# FEU3.net
KiCad netlist of a schematic drawn in EAGLE
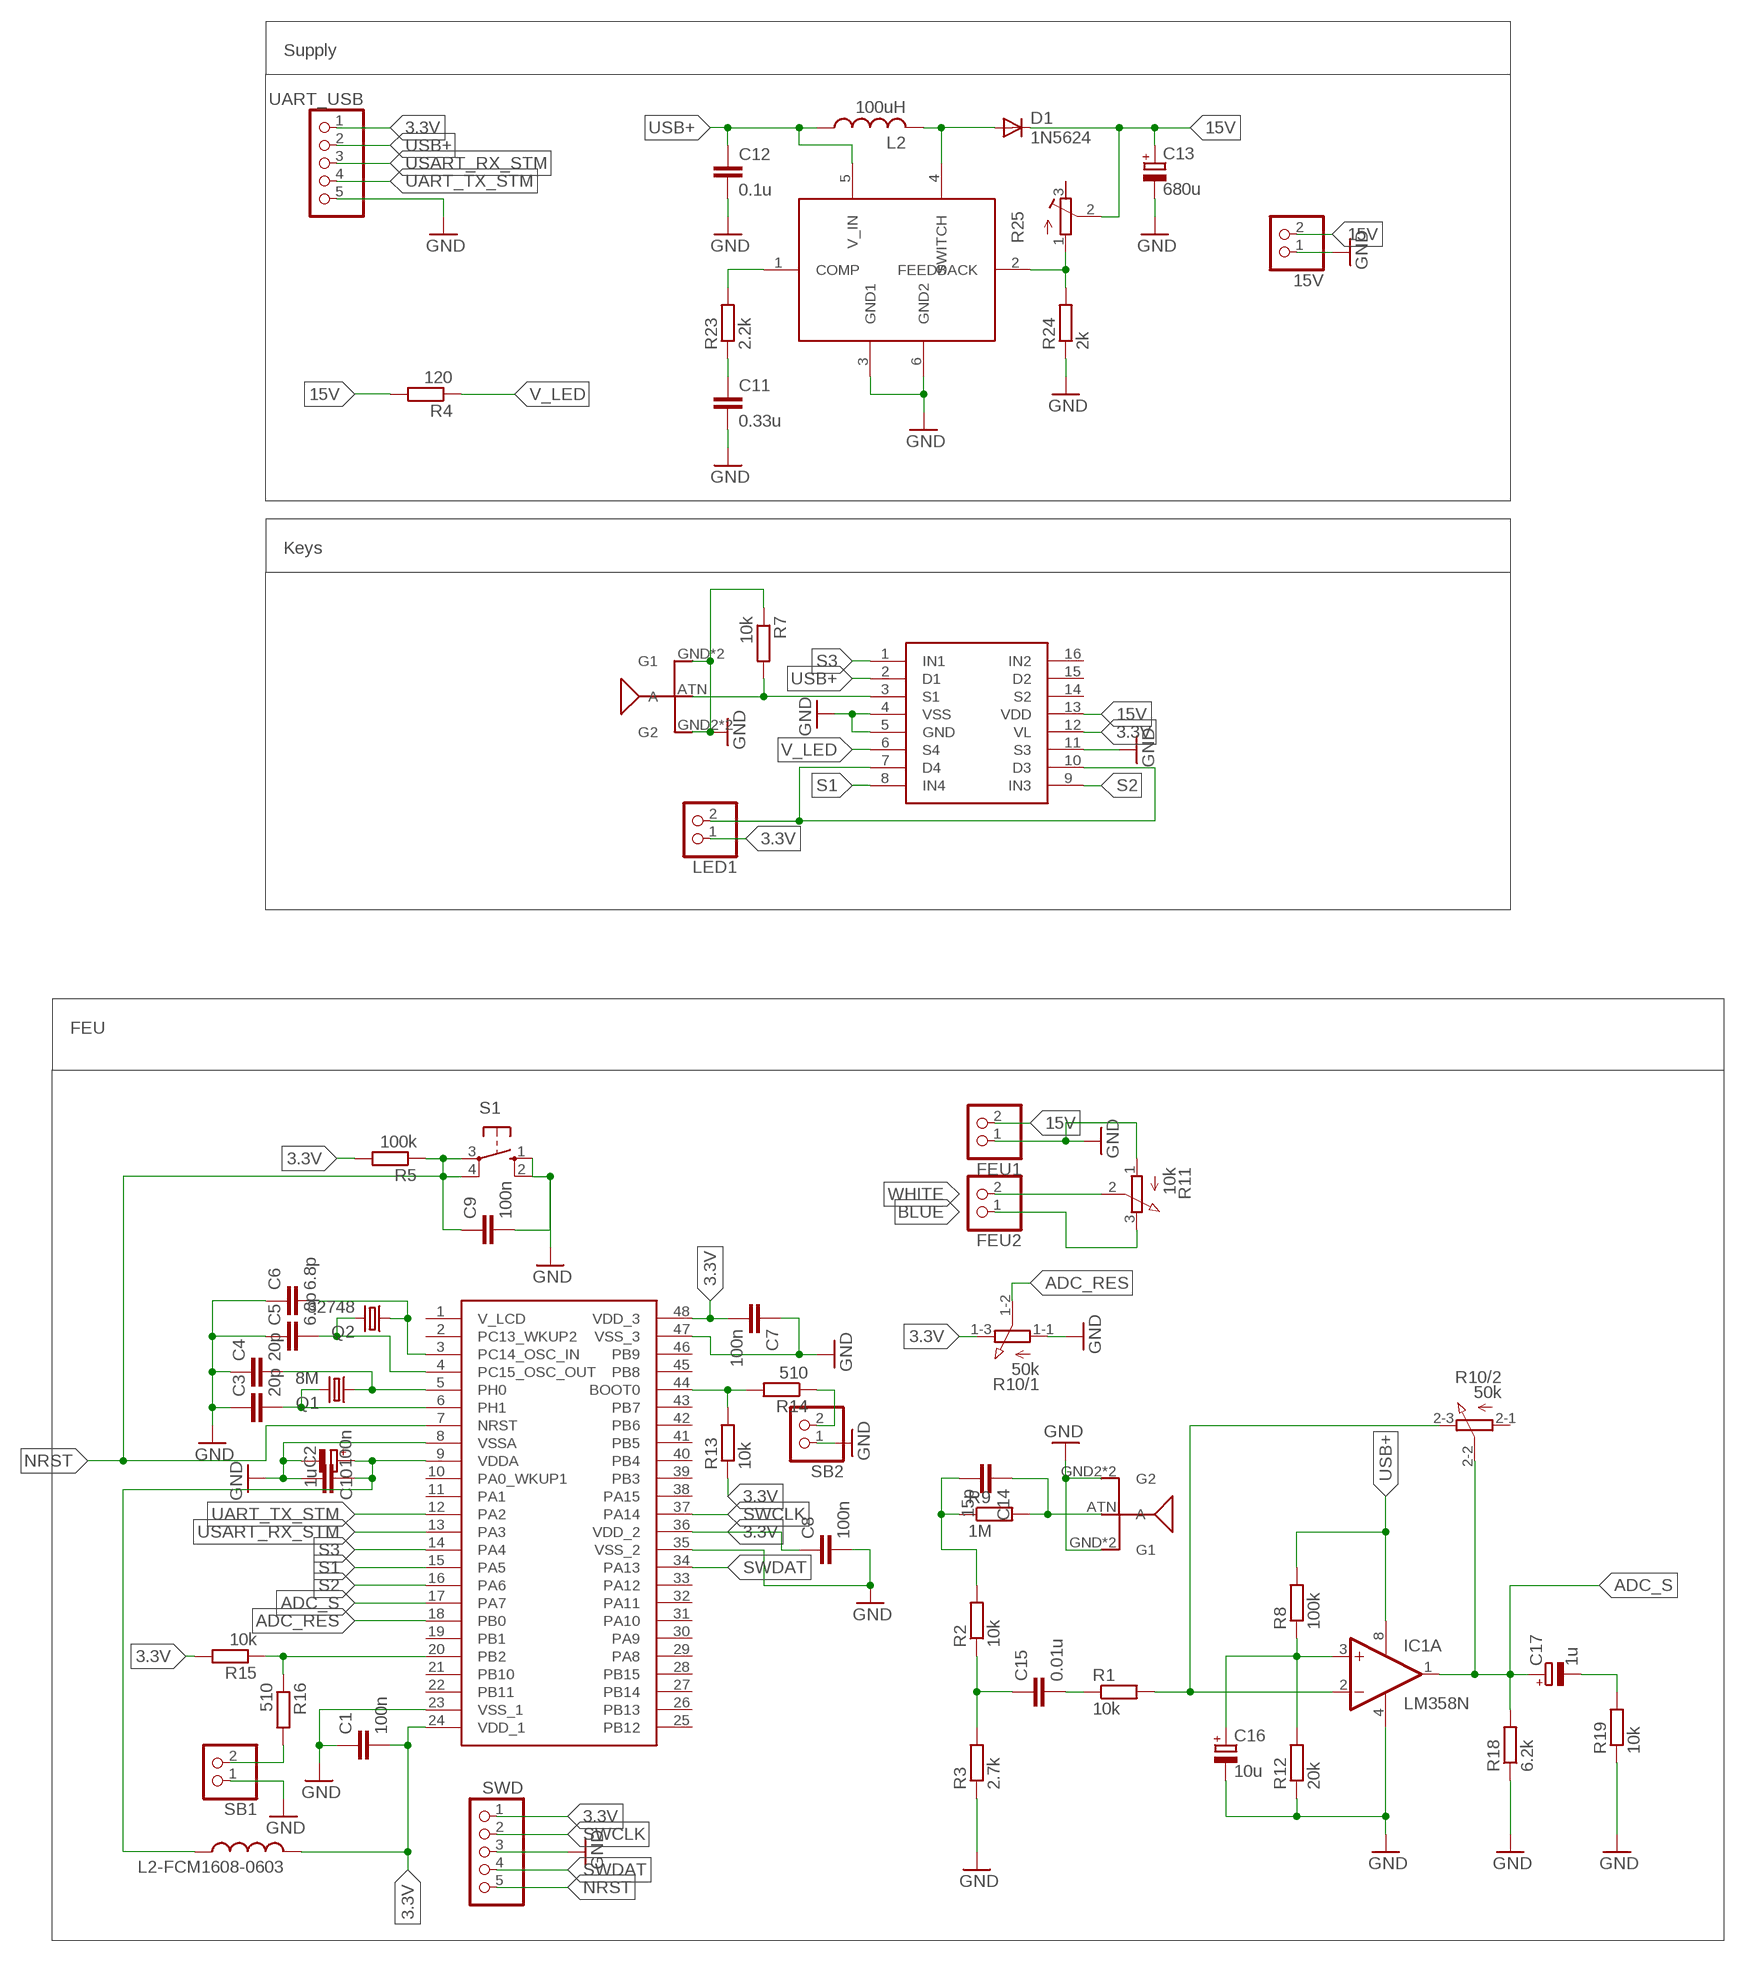
[diagram p0: schematic, sheet 1]

(export (version "E")
  (design (tool "Eeschema 10.0.6"))
  (components
    (comp (ref "15V")
      (value "PINHD-1X2")
      (footprint "eagle-import:1X02")
      (libsource (lib "eagle-import") (part "PINHD-1X2"))
    )
    (comp (ref "C1")
      (value "100n")
      (footprint "eagle-import:C0805")
      (libsource (lib "eagle-import") (part "C-EUC0805"))
    )
    (comp (ref "C2")
      (value "100n")
      (footprint "eagle-import:C0805")
      (libsource (lib "eagle-import") (part "C-EUC0805"))
    )
    (comp (ref "C3")
      (value "20p")
      (footprint "eagle-import:C0805")
      (libsource (lib "eagle-import") (part "C-EUC0805"))
    )
    (comp (ref "C4")
      (value "20p")
      (footprint "eagle-import:C0805")
      (libsource (lib "eagle-import") (part "C-EUC0805"))
    )
    (comp (ref "C5")
      (value "6.8p")
      (footprint "eagle-import:C0805")
      (libsource (lib "eagle-import") (part "C-EUC0805"))
    )
    (comp (ref "C6")
      (value "6.8p")
      (footprint "eagle-import:C0805")
      (libsource (lib "eagle-import") (part "C-EUC0805"))
    )
    (comp (ref "C7")
      (value "100n")
      (footprint "eagle-import:C0805")
      (libsource (lib "eagle-import") (part "C-EUC0805"))
    )
    (comp (ref "C8")
      (value "100n")
      (footprint "eagle-import:C0805")
      (libsource (lib "eagle-import") (part "C-EUC0805"))
    )
    (comp (ref "C9")
      (value "100n")
      (footprint "eagle-import:C0805")
      (libsource (lib "eagle-import") (part "C-EUC0805"))
    )
    (comp (ref "C10")
      (value "1u")
      (footprint "eagle-import:A_3216-18W")
      (libsource (lib "eagle-import") (part "CPOL-EUA/3216-18W"))
    )
    (comp (ref "C11")
      (value "0.33u")
      (footprint "eagle-import:C0805")
      (libsource (lib "eagle-import") (part "C-EUC0805"))
    )
    (comp (ref "C12")
      (value "0.1u")
      (footprint "eagle-import:C0805")
      (libsource (lib "eagle-import") (part "C-EUC0805"))
    )
    (comp (ref "C13")
      (value "680u")
      (footprint "eagle-import:E5-5")
      (libsource (lib "eagle-import") (part "CPOL-EUE5-5"))
    )
    (comp (ref "C14")
      (value "15p")
      (footprint "eagle-import:C0805")
      (libsource (lib "eagle-import") (part "C-EUC0805"))
    )
    (comp (ref "C15")
      (value "0.01u")
      (footprint "eagle-import:C0805")
      (libsource (lib "eagle-import") (part "C-EUC0805"))
    )
    (comp (ref "C16")
      (value "10u")
      (footprint "eagle-import:E3,5-8")
      (libsource (lib "eagle-import") (part "CPOL-EUE3.5-8"))
    )
    (comp (ref "C17")
      (value "1u")
      (footprint "eagle-import:E3,5-8")
      (libsource (lib "eagle-import") (part "CPOL-EUE3.5-8"))
    )
    (comp (ref "D1")
      (value "1N5624")
      (footprint "eagle-import:DO201-15")
      (libsource (lib "eagle-import") (part "1N5624"))
    )
    (comp (ref "FEU1")
      (value "PINHD-1X2")
      (footprint "eagle-import:1X02")
      (libsource (lib "eagle-import") (part "PINHD-1X2"))
    )
    (comp (ref "FEU2")
      (value "PINHD-1X2")
      (footprint "eagle-import:1X02")
      (libsource (lib "eagle-import") (part "PINHD-1X2"))
    )
    (comp (ref "IC1")
      (value "LM358N")
      (footprint "eagle-import:DIL08")
      (libsource (lib "eagle-import") (part "LM358N"))
    )
    (comp (ref "L2")
      (value "100uH")
      (footprint "eagle-import:0207_5V")
      (libsource (lib "eagle-import") (part "L-US0207/5V"))
    )
    (comp (ref "L2-FCM1608-0603")
      (value "L-USL3216C")
      (footprint "eagle-import:L3216C")
      (libsource (lib "eagle-import") (part "L-USL3216C"))
    )
    (comp (ref "LED1")
      (value "PINHD-1X2")
      (footprint "eagle-import:1X02")
      (libsource (lib "eagle-import") (part "PINHD-1X2"))
    )
    (comp (ref "Q1")
      (value "8M")
      (footprint "eagle-import:HC49_S")
      (fields (field (name "OC_FARNELL") "1667008"))
      (libsource (lib "eagle-import") (part "CRYSTALHC49S"))
    )
    (comp (ref "Q2")
      (value "32748")
      (footprint "eagle-import:TC26H")
      (libsource (lib "eagle-import") (part "CRYSTALTC26H"))
    )
    (comp (ref "R1")
      (value "10k")
      (footprint "eagle-import:R0805")
      (libsource (lib "eagle-import") (part "R-EU_R0805"))
    )
    (comp (ref "R2")
      (value "10k")
      (footprint "eagle-import:R0805")
      (libsource (lib "eagle-import") (part "R-EU_R0805"))
    )
    (comp (ref "R3")
      (value "2.7k")
      (footprint "eagle-import:R0805")
      (libsource (lib "eagle-import") (part "R-EU_R0805"))
    )
    (comp (ref "R4")
      (value "120")
      (footprint "eagle-import:R0805")
      (libsource (lib "eagle-import") (part "R-EU_R0805"))
    )
    (comp (ref "R5")
      (value "100k")
      (footprint "eagle-import:R0805")
      (libsource (lib "eagle-import") (part "R-EU_R0805"))
    )
    (comp (ref "R7")
      (value "10k")
      (footprint "eagle-import:R0805")
      (libsource (lib "eagle-import") (part "R-EU_R0805"))
    )
    (comp (ref "R8")
      (value "100k")
      (footprint "eagle-import:R0805")
      (libsource (lib "eagle-import") (part "R-EU_R0805"))
    )
    (comp (ref "R9")
      (value "1M")
      (footprint "eagle-import:R0805")
      (libsource (lib "eagle-import") (part "R-EU_R0805"))
    )
    (comp (ref "R10")
      (value "50k")
      (footprint "eagle-import:3RP_1610G")
      (libsource (lib "eagle-import") (part "3RP/1610G"))
    )
    (comp (ref "R11")
      (value "10k")
      (footprint "eagle-import:3RP_1610N")
      (libsource (lib "eagle-import") (part "3RP/1610N"))
    )
    (comp (ref "R12")
      (value "20k")
      (footprint "eagle-import:R0805")
      (libsource (lib "eagle-import") (part "R-EU_R0805"))
    )
    (comp (ref "R13")
      (value "10k")
      (footprint "eagle-import:R0805")
      (libsource (lib "eagle-import") (part "R-EU_R0805"))
    )
    (comp (ref "R14")
      (value "510")
      (footprint "eagle-import:R0805")
      (libsource (lib "eagle-import") (part "R-EU_R0805"))
    )
    (comp (ref "R15")
      (value "10k")
      (footprint "eagle-import:M0805")
      (libsource (lib "eagle-import") (part "R-EU_M0805"))
    )
    (comp (ref "R16")
      (value "510")
      (footprint "eagle-import:R0805")
      (libsource (lib "eagle-import") (part "R-EU_R0805"))
    )
    (comp (ref "R18")
      (value "6.2k")
      (footprint "eagle-import:R0805")
      (libsource (lib "eagle-import") (part "R-EU_R0805"))
    )
    (comp (ref "R19")
      (value "10k")
      (footprint "eagle-import:R0805")
      (libsource (lib "eagle-import") (part "R-EU_R0805"))
    )
    (comp (ref "R23")
      (value "2.2k")
      (footprint "eagle-import:R0805")
      (libsource (lib "eagle-import") (part "R-EU_R0805"))
    )
    (comp (ref "R24")
      (value "2k")
      (footprint "eagle-import:R0805")
      (libsource (lib "eagle-import") (part "R-EU_R0805"))
    )
    (comp (ref "R25")
      (value "R-TRIMM3339P")
      (footprint "eagle-import:RTRIM3339P")
      (libsource (lib "eagle-import") (part "R-TRIMM3339P"))
    )
    (comp (ref "S1")
      (value "10-XX")
      (footprint "eagle-import:B3F-10XX")
      (fields (field (name "MPN") "B3F-1000"))
      (libsource (lib "eagle-import") (part "10-XX"))
    )
    (comp (ref "SB1")
      (value "PINHD-1X2")
      (footprint "eagle-import:1X02")
      (libsource (lib "eagle-import") (part "PINHD-1X2"))
    )
    (comp (ref "SB2")
      (value "PINHD-1X2")
      (footprint "eagle-import:1X02")
      (libsource (lib "eagle-import") (part "PINHD-1X2"))
    )
    (comp (ref "SWD")
      (value "PINHD-1X5")
      (footprint "eagle-import:1X05")
      (libsource (lib "eagle-import") (part "PINHD-1X5"))
    )
    (comp (ref "U$1")
      (value "STM32L152C6")
      (footprint "eagle-import:LQFP48")
      (libsource (lib "eagle-import") (part "STM32L152C6"))
    )
    (comp (ref "U$2")
      (value "GSM_ANT")
      (footprint "eagle-import:GSM")
      (libsource (lib "eagle-import") (part "GSM_ANT"))
    )
    (comp (ref "U$3")
      (value "GSM_ANT")
      (footprint "eagle-import:GSM")
      (libsource (lib "eagle-import") (part "GSM_ANT"))
    )
    (comp (ref "U$4")
      (value "LM2577")
      (footprint "eagle-import:TO263-5")
      (libsource (lib "eagle-import") (part "LM2577"))
    )
    (comp (ref "U$5")
      (value "ADG433BN")
      (footprint "eagle-import:DIL16")
      (libsource (lib "eagle-import") (part "ADG433BN"))
    )
    (comp (ref "UART_USB")
      (value "PINHD-1X5")
      (footprint "eagle-import:1X05")
      (libsource (lib "eagle-import") (part "PINHD-1X5"))
    )
  )
  (nets
    (net (code "1") (name "3.3V") (class "Default")
      (node (ref "C1") (pin "2") (pinfunction "2_2") (pintype "passive"))
      (node (ref "C7") (pin "2") (pinfunction "2_2") (pintype "passive"))
      (node (ref "C8") (pin "1") (pinfunction "1_1") (pintype "passive"))
      (node (ref "L2-FCM1608-0603") (pin "2") (pinfunction "2_2") (pintype "passive"))
      (node (ref "LED1") (pin "1") (pinfunction "1_1") (pintype "passive"))
      (node (ref "R10") (pin "1-3") (pinfunction "E_1-3") (pintype "passive"))
      (node (ref "R13") (pin "1") (pinfunction "1_1") (pintype "passive"))
      (node (ref "R15") (pin "2") (pinfunction "2_2") (pintype "passive"))
      (node (ref "R5") (pin "2") (pinfunction "2_2") (pintype "passive"))
      (node (ref "SWD") (pin "1") (pinfunction "1_1") (pintype "passive"))
      (node (ref "U$1") (pin "24") (pinfunction "VDD_1_24") (pintype "bidirectional"))
      (node (ref "U$1") (pin "36") (pinfunction "VDD_2_36") (pintype "bidirectional"))
      (node (ref "U$1") (pin "48") (pinfunction "VDD_3_48") (pintype "bidirectional"))
      (node (ref "U$5") (pin "12") (pinfunction "VL_12") (pintype "bidirectional"))
      (node (ref "UART_USB") (pin "1") (pinfunction "1_1") (pintype "passive"))
    )
    (net (code "2") (name "15V") (class "Default")
      (node (ref "15V") (pin "2") (pinfunction "2_2") (pintype "passive"))
      (node (ref "C13") (pin "+") (pinfunction "+_+") (pintype "passive"))
      (node (ref "D1") (pin "C") (pinfunction "C_C") (pintype "passive"))
      (node (ref "FEU1") (pin "2") (pinfunction "2_2") (pintype "passive"))
      (node (ref "R25") (pin "2") (pinfunction "S_2") (pintype "passive"))
      (node (ref "R4") (pin "2") (pinfunction "2_2") (pintype "passive"))
      (node (ref "U$5") (pin "13") (pinfunction "VDD_13") (pintype "bidirectional"))
    )
    (net (code "3") (name "ADC_RES") (class "Default")
      (node (ref "R10") (pin "1-2") (pinfunction "S_1-2") (pintype "passive"))
      (node (ref "U$1") (pin "18") (pinfunction "PB0_18") (pintype "bidirectional"))
    )
    (net (code "4") (name "ADC_S") (class "Default")
      (node (ref "C17") (pin "+") (pinfunction "+_+") (pintype "passive"))
      (node (ref "IC1") (pin "1") (pinfunction "OUT_1") (pintype "output"))
      (node (ref "R10") (pin "2-2") (pinfunction "S_2-2") (pintype "passive"))
      (node (ref "R18") (pin "2") (pinfunction "2_2") (pintype "passive"))
      (node (ref "U$1") (pin "17") (pinfunction "PA7_17") (pintype "bidirectional"))
    )
    (net (code "5") (name "BLUE") (class "Default")
      (node (ref "FEU2") (pin "1") (pinfunction "1_1") (pintype "passive"))
      (node (ref "R11") (pin "3") (pinfunction "E_3") (pintype "passive"))
    )
    (net (code "6") (name "GND") (class "Default")
      (node (ref "15V") (pin "1") (pinfunction "1_1") (pintype "passive"))
      (node (ref "C1") (pin "1") (pinfunction "1_1") (pintype "passive"))
      (node (ref "C10") (pin "-") (pinfunction "-_-") (pintype "passive"))
      (node (ref "C11") (pin "2") (pinfunction "2_2") (pintype "passive"))
      (node (ref "C12") (pin "2") (pinfunction "2_2") (pintype "passive"))
      (node (ref "C13") (pin "-") (pinfunction "-_-") (pintype "passive"))
      (node (ref "C16") (pin "-") (pinfunction "-_-") (pintype "passive"))
      (node (ref "C2") (pin "1") (pinfunction "1_1") (pintype "passive"))
      (node (ref "C3") (pin "1") (pinfunction "1_1") (pintype "passive"))
      (node (ref "C4") (pin "1") (pinfunction "1_1") (pintype "passive"))
      (node (ref "C5") (pin "1") (pinfunction "1_1") (pintype "passive"))
      (node (ref "C6") (pin "1") (pinfunction "1_1") (pintype "passive"))
      (node (ref "C7") (pin "1") (pinfunction "1_1") (pintype "passive"))
      (node (ref "C8") (pin "2") (pinfunction "2_2") (pintype "passive"))
      (node (ref "C9") (pin "2") (pinfunction "2_2") (pintype "passive"))
      (node (ref "FEU1") (pin "1") (pinfunction "1_1") (pintype "passive"))
      (node (ref "IC1") (pin "4") (pinfunction "V-_4") (pintype "power_in"))
      (node (ref "R10") (pin "1-1") (pinfunction "A_1-1") (pintype "passive"))
      (node (ref "R11") (pin "1") (pinfunction "A_1") (pintype "passive"))
      (node (ref "R12") (pin "1") (pinfunction "1_1") (pintype "passive"))
      (node (ref "R18") (pin "1") (pinfunction "1_1") (pintype "passive"))
      (node (ref "R19") (pin "1") (pinfunction "1_1") (pintype "passive"))
      (node (ref "R24") (pin "1") (pinfunction "1_1") (pintype "passive"))
      (node (ref "R3") (pin "1") (pinfunction "1_1") (pintype "passive"))
      (node (ref "R7") (pin "1") (pinfunction "1_1") (pintype "passive"))
      (node (ref "S1") (pin "1") (pinfunction "S_1") (pintype "passive"))
      (node (ref "S1") (pin "2") (pinfunction "S1_2") (pintype "passive"))
      (node (ref "SB1") (pin "1") (pinfunction "1_1") (pintype "passive"))
      (node (ref "SB2") (pin "1") (pinfunction "1_1") (pintype "passive"))
      (node (ref "SWD") (pin "3") (pinfunction "3_3") (pintype "passive"))
      (node (ref "U$1") (pin "23") (pinfunction "VSS_1_23") (pintype "bidirectional"))
      (node (ref "U$1") (pin "35") (pinfunction "VSS_2_35") (pintype "bidirectional"))
      (node (ref "U$1") (pin "47") (pinfunction "VSS_3_47") (pintype "bidirectional"))
      (node (ref "U$1") (pin "8") (pinfunction "VSSA_8") (pintype "bidirectional"))
      (node (ref "U$2") (pin "GND") (pinfunction "G1_GND") (pintype "bidirectional"))
      (node (ref "U$2") (pin "GND1") (pinfunction "G1_GND1") (pintype "bidirectional"))
      (node (ref "U$2") (pin "GND2") (pinfunction "G2_GND2") (pintype "bidirectional"))
      (node (ref "U$2") (pin "GND3") (pinfunction "G2_GND3") (pintype "bidirectional"))
      (node (ref "U$3") (pin "GND") (pinfunction "G1_GND") (pintype "bidirectional"))
      (node (ref "U$3") (pin "GND1") (pinfunction "G1_GND1") (pintype "bidirectional"))
      (node (ref "U$3") (pin "GND2") (pinfunction "G2_GND2") (pintype "bidirectional"))
      (node (ref "U$3") (pin "GND3") (pinfunction "G2_GND3") (pintype "bidirectional"))
      (node (ref "U$4") (pin "3") (pinfunction "GND1_3") (pintype "bidirectional"))
      (node (ref "U$4") (pin "6") (pinfunction "GND2_6") (pintype "bidirectional"))
      (node (ref "U$5") (pin "11") (pinfunction "S3_11") (pintype "bidirectional"))
      (node (ref "U$5") (pin "4") (pinfunction "VSS_4") (pintype "bidirectional"))
      (node (ref "U$5") (pin "5") (pinfunction "GND_5") (pintype "bidirectional"))
      (node (ref "UART_USB") (pin "5") (pinfunction "5_5") (pintype "passive"))
    )
    (net (code "7") (name "NRST") (class "Default")
      (node (ref "C9") (pin "1") (pinfunction "1_1") (pintype "passive"))
      (node (ref "R5") (pin "1") (pinfunction "1_1") (pintype "passive"))
      (node (ref "S1") (pin "3") (pinfunction "P_3") (pintype "passive"))
      (node (ref "S1") (pin "4") (pinfunction "P1_4") (pintype "passive"))
      (node (ref "SWD") (pin "5") (pinfunction "5_5") (pintype "passive"))
      (node (ref "U$1") (pin "7") (pinfunction "NRST_7") (pintype "bidirectional"))
    )
    (net (code "8") (name "Net-(C11-Pad1)") (class "Default")
      (node (ref "C11") (pin "1") (pinfunction "1_1") (pintype "passive"))
      (node (ref "R23") (pin "1") (pinfunction "1_1") (pintype "passive"))
    )
    (net (code "9") (name "Net-(C14-Pad2)") (class "Default")
      (node (ref "C14") (pin "2") (pinfunction "2_2") (pintype "passive"))
      (node (ref "R2") (pin "2") (pinfunction "2_2") (pintype "passive"))
      (node (ref "R9") (pin "1") (pinfunction "1_1") (pintype "passive"))
    )
    (net (code "10") (name "Net-(C15-Pad1)") (class "Default")
      (node (ref "C15") (pin "1") (pinfunction "1_1") (pintype "passive"))
      (node (ref "R2") (pin "1") (pinfunction "1_1") (pintype "passive"))
      (node (ref "R3") (pin "2") (pinfunction "2_2") (pintype "passive"))
    )
    (net (code "11") (name "Net-(C15-Pad2)") (class "Default")
      (node (ref "C15") (pin "2") (pinfunction "2_2") (pintype "passive"))
      (node (ref "R1") (pin "1") (pinfunction "1_1") (pintype "passive"))
    )
    (net (code "12") (name "Net-(C17-Pad-)") (class "Default")
      (node (ref "C17") (pin "-") (pinfunction "-_-") (pintype "passive"))
      (node (ref "R19") (pin "2") (pinfunction "2_2") (pintype "passive"))
    )
    (net (code "13") (name "Net-(IC1A-+IN)") (class "Default")
      (node (ref "C16") (pin "+") (pinfunction "+_+") (pintype "passive"))
      (node (ref "IC1") (pin "3") (pinfunction "+IN_3") (pintype "input"))
      (node (ref "R12") (pin "2") (pinfunction "2_2") (pintype "passive"))
      (node (ref "R8") (pin "1") (pinfunction "1_1") (pintype "passive"))
    )
    (net (code "14") (name "Net-(IC1A--IN)") (class "Default")
      (node (ref "IC1") (pin "2") (pinfunction "-IN_2") (pintype "input"))
      (node (ref "R1") (pin "2") (pinfunction "2_2") (pintype "passive"))
      (node (ref "R10") (pin "2-3") (pinfunction "E_2-3") (pintype "passive"))
    )
    (net (code "15") (name "Net-(R14-Pad1)") (class "Default")
      (node (ref "R14") (pin "1") (pinfunction "1_1") (pintype "passive"))
      (node (ref "SB2") (pin "2") (pinfunction "2_2") (pintype "passive"))
    )
    (net (code "16") (name "Net-(R16-Pad2)") (class "Default")
      (node (ref "R16") (pin "2") (pinfunction "2_2") (pintype "passive"))
      (node (ref "SB1") (pin "2") (pinfunction "2_2") (pintype "passive"))
    )
    (net (code "17") (name "Net-(R25-E)") (class "Default")
      (node (ref "R24") (pin "2") (pinfunction "2_2") (pintype "passive"))
      (node (ref "R25") (pin "1") (pinfunction "E_1") (pintype "passive"))
      (node (ref "U$4") (pin "2") (pinfunction "FEEDBACK_2") (pintype "bidirectional"))
    )
    (net (code "18") (name "Net-(U$1-BOOT0)") (class "Default")
      (node (ref "R13") (pin "2") (pinfunction "2_2") (pintype "passive"))
      (node (ref "R14") (pin "2") (pinfunction "2_2") (pintype "passive"))
      (node (ref "U$1") (pin "44") (pinfunction "BOOT0_44") (pintype "bidirectional"))
    )
    (net (code "19") (name "Net-(U$1-PB2)") (class "Default")
      (node (ref "R15") (pin "1") (pinfunction "1_1") (pintype "passive"))
      (node (ref "R16") (pin "1") (pinfunction "1_1") (pintype "passive"))
      (node (ref "U$1") (pin "20") (pinfunction "PB2_20") (pintype "bidirectional"))
    )
    (net (code "20") (name "Net-(U$1-PC14_OSC_IN)") (class "Default")
      (node (ref "C6") (pin "2") (pinfunction "2_2") (pintype "passive"))
      (node (ref "Q2") (pin "1") (pinfunction "1_1") (pintype "passive"))
      (node (ref "U$1") (pin "3") (pinfunction "PC14_OSC_IN_3") (pintype "bidirectional"))
    )
    (net (code "21") (name "Net-(U$1-PC15_OSC_OUT)") (class "Default")
      (node (ref "C5") (pin "2") (pinfunction "2_2") (pintype "passive"))
      (node (ref "Q2") (pin "2") (pinfunction "2_2") (pintype "passive"))
      (node (ref "U$1") (pin "4") (pinfunction "PC15_OSC_OUT_4") (pintype "bidirectional"))
    )
    (net (code "22") (name "Net-(U$1-PH0)") (class "Default")
      (node (ref "C4") (pin "2") (pinfunction "2_2") (pintype "passive"))
      (node (ref "Q1") (pin "1") (pinfunction "1_1") (pintype "passive"))
      (node (ref "U$1") (pin "5") (pinfunction "PH0_5") (pintype "bidirectional"))
    )
    (net (code "23") (name "Net-(U$1-PH1)") (class "Default")
      (node (ref "C3") (pin "2") (pinfunction "2_2") (pintype "passive"))
      (node (ref "Q1") (pin "2") (pinfunction "2_2") (pintype "passive"))
      (node (ref "U$1") (pin "6") (pinfunction "PH1_6") (pintype "bidirectional"))
    )
    (net (code "24") (name "Net-(U$1-VDDA)") (class "Default")
      (node (ref "C10") (pin "+") (pinfunction "+_+") (pintype "passive"))
      (node (ref "C2") (pin "2") (pinfunction "2_2") (pintype "passive"))
      (node (ref "L2-FCM1608-0603") (pin "1") (pinfunction "1_1") (pintype "passive"))
      (node (ref "U$1") (pin "9") (pinfunction "VDDA_9") (pintype "bidirectional"))
    )
    (net (code "25") (name "Net-(U$2-A)") (class "Default")
      (node (ref "C14") (pin "1") (pinfunction "1_1") (pintype "passive"))
      (node (ref "R9") (pin "2") (pinfunction "2_2") (pintype "passive"))
      (node (ref "U$2") (pin "ATN") (pinfunction "A_ATN") (pintype "bidirectional"))
    )
    (net (code "26") (name "Net-(U$3-A)") (class "Default")
      (node (ref "R7") (pin "2") (pinfunction "2_2") (pintype "passive"))
      (node (ref "U$3") (pin "ATN") (pinfunction "A_ATN") (pintype "bidirectional"))
      (node (ref "U$5") (pin "3") (pinfunction "S1_3") (pintype "bidirectional"))
    )
    (net (code "27") (name "Net-(U$4-COMP)") (class "Default")
      (node (ref "R23") (pin "2") (pinfunction "2_2") (pintype "passive"))
      (node (ref "U$4") (pin "1") (pinfunction "COMP_1") (pintype "bidirectional"))
    )
    (net (code "28") (name "Net-(U$4-SWITCH)") (class "Default")
      (node (ref "D1") (pin "A") (pinfunction "A_A") (pintype "passive"))
      (node (ref "L2") (pin "2") (pinfunction "2_2") (pintype "passive"))
      (node (ref "U$4") (pin "4") (pinfunction "SWITCH_4") (pintype "bidirectional"))
    )
    (net (code "29") (name "Net-(U$5-D3)") (class "Default")
      (node (ref "LED1") (pin "2") (pinfunction "2_2") (pintype "passive"))
      (node (ref "U$5") (pin "10") (pinfunction "D3_10") (pintype "bidirectional"))
      (node (ref "U$5") (pin "7") (pinfunction "D4_7") (pintype "bidirectional"))
    )
    (net (code "30") (name "S1") (class "Default")
      (node (ref "U$1") (pin "15") (pinfunction "PA5_15") (pintype "bidirectional"))
      (node (ref "U$5") (pin "8") (pinfunction "IN4_8") (pintype "bidirectional"))
    )
    (net (code "31") (name "S2") (class "Default")
      (node (ref "U$1") (pin "16") (pinfunction "PA6_16") (pintype "bidirectional"))
      (node (ref "U$5") (pin "9") (pinfunction "IN3_9") (pintype "bidirectional"))
    )
    (net (code "32") (name "S3") (class "Default")
      (node (ref "U$1") (pin "14") (pinfunction "PA4_14") (pintype "bidirectional"))
      (node (ref "U$5") (pin "1") (pinfunction "IN1_1") (pintype "bidirectional"))
    )
    (net (code "33") (name "SWCLK") (class "Default")
      (node (ref "SWD") (pin "2") (pinfunction "2_2") (pintype "passive"))
      (node (ref "U$1") (pin "37") (pinfunction "PA14_37") (pintype "bidirectional"))
    )
    (net (code "34") (name "SWDAT") (class "Default")
      (node (ref "SWD") (pin "4") (pinfunction "4_4") (pintype "passive"))
      (node (ref "U$1") (pin "34") (pinfunction "PA13_34") (pintype "bidirectional"))
    )
    (net (code "35") (name "UART_TX_STM") (class "Default")
      (node (ref "U$1") (pin "12") (pinfunction "PA2_12") (pintype "bidirectional"))
      (node (ref "UART_USB") (pin "4") (pinfunction "4_4") (pintype "passive"))
    )
    (net (code "36") (name "USART_RX_STM") (class "Default")
      (node (ref "U$1") (pin "13") (pinfunction "PA3_13") (pintype "bidirectional"))
      (node (ref "UART_USB") (pin "3") (pinfunction "3_3") (pintype "passive"))
    )
    (net (code "37") (name "USB+") (class "Default")
      (node (ref "C12") (pin "1") (pinfunction "1_1") (pintype "passive"))
      (node (ref "IC1") (pin "8") (pinfunction "V+_8") (pintype "power_in"))
      (node (ref "L2") (pin "1") (pinfunction "1_1") (pintype "passive"))
      (node (ref "R8") (pin "2") (pinfunction "2_2") (pintype "passive"))
      (node (ref "U$4") (pin "5") (pinfunction "V_IN_5") (pintype "bidirectional"))
      (node (ref "U$5") (pin "2") (pinfunction "D1_2") (pintype "bidirectional"))
      (node (ref "UART_USB") (pin "2") (pinfunction "2_2") (pintype "passive"))
    )
    (net (code "38") (name "V_LED") (class "Default")
      (node (ref "R4") (pin "1") (pinfunction "1_1") (pintype "passive"))
      (node (ref "U$5") (pin "6") (pinfunction "S4_6") (pintype "bidirectional"))
    )
    (net (code "39") (name "WHITE") (class "Default")
      (node (ref "FEU2") (pin "2") (pinfunction "2_2") (pintype "passive"))
      (node (ref "R11") (pin "2") (pinfunction "S_2") (pintype "passive"))
    )
    (net (code "40") (name "unconnected-(R10B-A-Pad2-1)") (class "Default")
      (node (ref "R10") (pin "2-1") (pinfunction "A_2-1") (pintype "passive"))
    )
    (net (code "41") (name "unconnected-(R25-A-Pad3)") (class "Default")
      (node (ref "R25") (pin "3") (pinfunction "A_3") (pintype "passive"))
    )
    (net (code "42") (name "unconnected-(U$1-PA0_WKUP1-Pad10)") (class "Default")
      (node (ref "U$1") (pin "10") (pinfunction "PA0_WKUP1_10") (pintype "bidirectional"))
    )
    (net (code "43") (name "unconnected-(U$1-PA1-Pad11)") (class "Default")
      (node (ref "U$1") (pin "11") (pinfunction "PA1_11") (pintype "bidirectional"))
    )
    (net (code "44") (name "unconnected-(U$1-PA8-Pad29)") (class "Default")
      (node (ref "U$1") (pin "29") (pinfunction "PA8_29") (pintype "bidirectional"))
    )
    (net (code "45") (name "unconnected-(U$1-PA9-Pad30)") (class "Default")
      (node (ref "U$1") (pin "30") (pinfunction "PA9_30") (pintype "bidirectional"))
    )
    (net (code "46") (name "unconnected-(U$1-PA10-Pad31)") (class "Default")
      (node (ref "U$1") (pin "31") (pinfunction "PA10_31") (pintype "bidirectional"))
    )
    (net (code "47") (name "unconnected-(U$1-PA11-Pad32)") (class "Default")
      (node (ref "U$1") (pin "32") (pinfunction "PA11_32") (pintype "bidirectional"))
    )
    (net (code "48") (name "unconnected-(U$1-PA12-Pad33)") (class "Default")
      (node (ref "U$1") (pin "33") (pinfunction "PA12_33") (pintype "bidirectional"))
    )
    (net (code "49") (name "unconnected-(U$1-PA15-Pad38)") (class "Default")
      (node (ref "U$1") (pin "38") (pinfunction "PA15_38") (pintype "bidirectional"))
    )
    (net (code "50") (name "unconnected-(U$1-PB1-Pad19)") (class "Default")
      (node (ref "U$1") (pin "19") (pinfunction "PB1_19") (pintype "bidirectional"))
    )
    (net (code "51") (name "unconnected-(U$1-PB3-Pad39)") (class "Default")
      (node (ref "U$1") (pin "39") (pinfunction "PB3_39") (pintype "bidirectional"))
    )
    (net (code "52") (name "unconnected-(U$1-PB4-Pad40)") (class "Default")
      (node (ref "U$1") (pin "40") (pinfunction "PB4_40") (pintype "bidirectional"))
    )
    (net (code "53") (name "unconnected-(U$1-PB5-Pad41)") (class "Default")
      (node (ref "U$1") (pin "41") (pinfunction "PB5_41") (pintype "bidirectional"))
    )
    (net (code "54") (name "unconnected-(U$1-PB6-Pad42)") (class "Default")
      (node (ref "U$1") (pin "42") (pinfunction "PB6_42") (pintype "bidirectional"))
    )
    (net (code "55") (name "unconnected-(U$1-PB7-Pad43)") (class "Default")
      (node (ref "U$1") (pin "43") (pinfunction "PB7_43") (pintype "bidirectional"))
    )
    (net (code "56") (name "unconnected-(U$1-PB8-Pad45)") (class "Default")
      (node (ref "U$1") (pin "45") (pinfunction "PB8_45") (pintype "bidirectional"))
    )
    (net (code "57") (name "unconnected-(U$1-PB9-Pad46)") (class "Default")
      (node (ref "U$1") (pin "46") (pinfunction "PB9_46") (pintype "bidirectional"))
    )
    (net (code "58") (name "unconnected-(U$1-PB10-Pad21)") (class "Default")
      (node (ref "U$1") (pin "21") (pinfunction "PB10_21") (pintype "bidirectional"))
    )
    (net (code "59") (name "unconnected-(U$1-PB11-Pad22)") (class "Default")
      (node (ref "U$1") (pin "22") (pinfunction "PB11_22") (pintype "bidirectional"))
    )
    (net (code "60") (name "unconnected-(U$1-PB12-Pad25)") (class "Default")
      (node (ref "U$1") (pin "25") (pinfunction "PB12_25") (pintype "bidirectional"))
    )
    (net (code "61") (name "unconnected-(U$1-PB13-Pad26)") (class "Default")
      (node (ref "U$1") (pin "26") (pinfunction "PB13_26") (pintype "bidirectional"))
    )
    (net (code "62") (name "unconnected-(U$1-PB14-Pad27)") (class "Default")
      (node (ref "U$1") (pin "27") (pinfunction "PB14_27") (pintype "bidirectional"))
    )
    (net (code "63") (name "unconnected-(U$1-PB15-Pad28)") (class "Default")
      (node (ref "U$1") (pin "28") (pinfunction "PB15_28") (pintype "bidirectional"))
    )
    (net (code "64") (name "unconnected-(U$1-PC13_WKUP2-Pad2)") (class "Default")
      (node (ref "U$1") (pin "2") (pinfunction "PC13_WKUP2_2") (pintype "bidirectional"))
    )
    (net (code "65") (name "unconnected-(U$1-V_LCD-Pad1)") (class "Default")
      (node (ref "U$1") (pin "1") (pinfunction "V_LCD_1") (pintype "bidirectional"))
    )
    (net (code "66") (name "unconnected-(U$5-D2-Pad15)") (class "Default")
      (node (ref "U$5") (pin "15") (pinfunction "D2_15") (pintype "bidirectional"))
    )
    (net (code "67") (name "unconnected-(U$5-IN2-Pad16)") (class "Default")
      (node (ref "U$5") (pin "16") (pinfunction "IN2_16") (pintype "bidirectional"))
    )
    (net (code "68") (name "unconnected-(U$5-S2-Pad14)") (class "Default")
      (node (ref "U$5") (pin "14") (pinfunction "S2_14") (pintype "bidirectional"))
    )
  )
)
